# BuckConv.net
KiCad netlist of a schematic drawn in Altium Designer
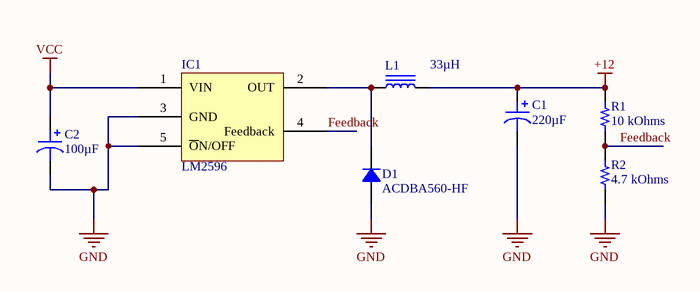
[diagram p0: BuckConv.SchDoc]

(export (version "E")
  (design (tool "Eeschema 10.0.6"))
  (components
    (comp (ref "C1")
      (value "220µF")
      (footprint "CAP TH ALUM ELEC D8.00mm S3.50mm H12.50mm")
      (description "CAP ALUM 220UF 20% 35V RADIAL")
      (fields
        (field (name "PART NUMBER") "ECA-1VM221")
        (field (name "MANUFACTURER") "Panasonic Electronic Components")
      )
      (libsource (lib "Celestial Altium Library - altium_library") (part "Polarised Capacitor"))
    )
    (comp (ref "C2")
      (value "100µF")
      (footprint "CAP TH ALUM ELEC D8.00mm S3.50mm H12.50mm")
      (description "CAP ALUM 100UF 20% 63V RADIAL")
      (fields
        (field (name "PART NUMBER") "ECA-1JM101")
        (field (name "MANUFACTURER") "Panasonic Electronic Components")
      )
      (libsource (lib "Celestial Altium Library - altium_library") (part "Polarised Capacitor"))
    )
    (comp (ref "D1")
      (value "ACDBA560-HF")
      (footprint "DO214AC SMA")
      (description "DIODE SCHOTTKY 60V 5A DO214AC")
      (fields (field (name "MANUFACTURER") "Comchip Technology"))
      (libsource (lib "Celestial Altium Library - altium_library") (part "Diode"))
    )
    (comp (ref "IC1") (value "LM2596") (footprint "D2PAK") (libsource (lib "BuckConv") (part "LM2596")))
    (comp (ref "L1")
      (value "33µH")
      (footprint "BOURNS SRR1280")
      (description "FIXED IND 33UH 3.5A 57 MOHM SMD")
      (fields (field (name "PART NUMBER") "SRR1280-330M") (field (name "MANUFACTURER") "Bourns Inc."))
      (libsource (lib "Celestial Altium Library - altium_library") (part "Inductor"))
    )
    (comp (ref "R1")
      (value "10 kOhms")
      (footprint "RES 0805_2012")
      (description "RES SMD 10K OHM 1% 1/10W 0805")
      (fields
        (field (name "PART NUMBER") "Y162910K0000F9R")
        (field (name "MANUFACTURER") "Vishay Foil Resistors (Division of Vishay Precision Group)")
      )
      (libsource (lib "Celestial Altium Library - altium_library") (part "Resistor"))
    )
    (comp (ref "R2")
      (value "4.7 kOhms")
      (footprint "RES 0805_2012")
      (description "CRGP 0805 4K7 1%")
      (fields
        (field (name "PART NUMBER") "CRGP0805F4K7")
        (field (name "MANUFACTURER") "TE Connectivity Passive Product")
      )
      (libsource (lib "Celestial Altium Library - altium_library") (part "Resistor"))
    )
  )
  (nets
    (net (code "1") (name "+12") (class "Default")
      (node (ref "C1") (pin "1") (pinfunction "1_1") (pintype "passive"))
      (node (ref "L1") (pin "2") (pinfunction "2_2") (pintype "passive"))
      (node (ref "R1") (pin "2") (pinfunction "2_2") (pintype "passive"))
    )
    (net (code "2") (name "/Feedback") (class "Default")
      (node (ref "IC1") (pin "4") (pinfunction "Feedback_4") (pintype "passive"))
      (node (ref "R1") (pin "1") (pinfunction "1_1") (pintype "passive"))
      (node (ref "R2") (pin "2") (pinfunction "2_2") (pintype "passive"))
    )
    (net (code "3") (name "GND") (class "Default")
      (node (ref "C1") (pin "2") (pinfunction "2_2") (pintype "passive"))
      (node (ref "C2") (pin "2") (pinfunction "2_2") (pintype "passive"))
      (node (ref "D1") (pin "1") (pinfunction "1_1") (pintype "passive"))
      (node (ref "IC1") (pin "3") (pinfunction "GND_3") (pintype "passive"))
      (node (ref "IC1") (pin "5") (pinfunction "~{O}N/OFF_5") (pintype "passive"))
      (node (ref "R2") (pin "1") (pinfunction "1_1") (pintype "passive"))
    )
    (net (code "4") (name "Net-(IC1-OUT)") (class "Default")
      (node (ref "D1") (pin "2") (pinfunction "2_2") (pintype "passive"))
      (node (ref "IC1") (pin "2") (pinfunction "OUT_2") (pintype "passive"))
      (node (ref "L1") (pin "1") (pinfunction "1_1") (pintype "passive"))
    )
    (net (code "5") (name "VCC") (class "Default")
      (node (ref "C2") (pin "1") (pinfunction "1_1") (pintype "passive"))
      (node (ref "IC1") (pin "1") (pinfunction "VIN_1") (pintype "passive"))
    )
  )
)
